# BreaV7.net
KiCad netlist of a schematic drawn in EAGLE
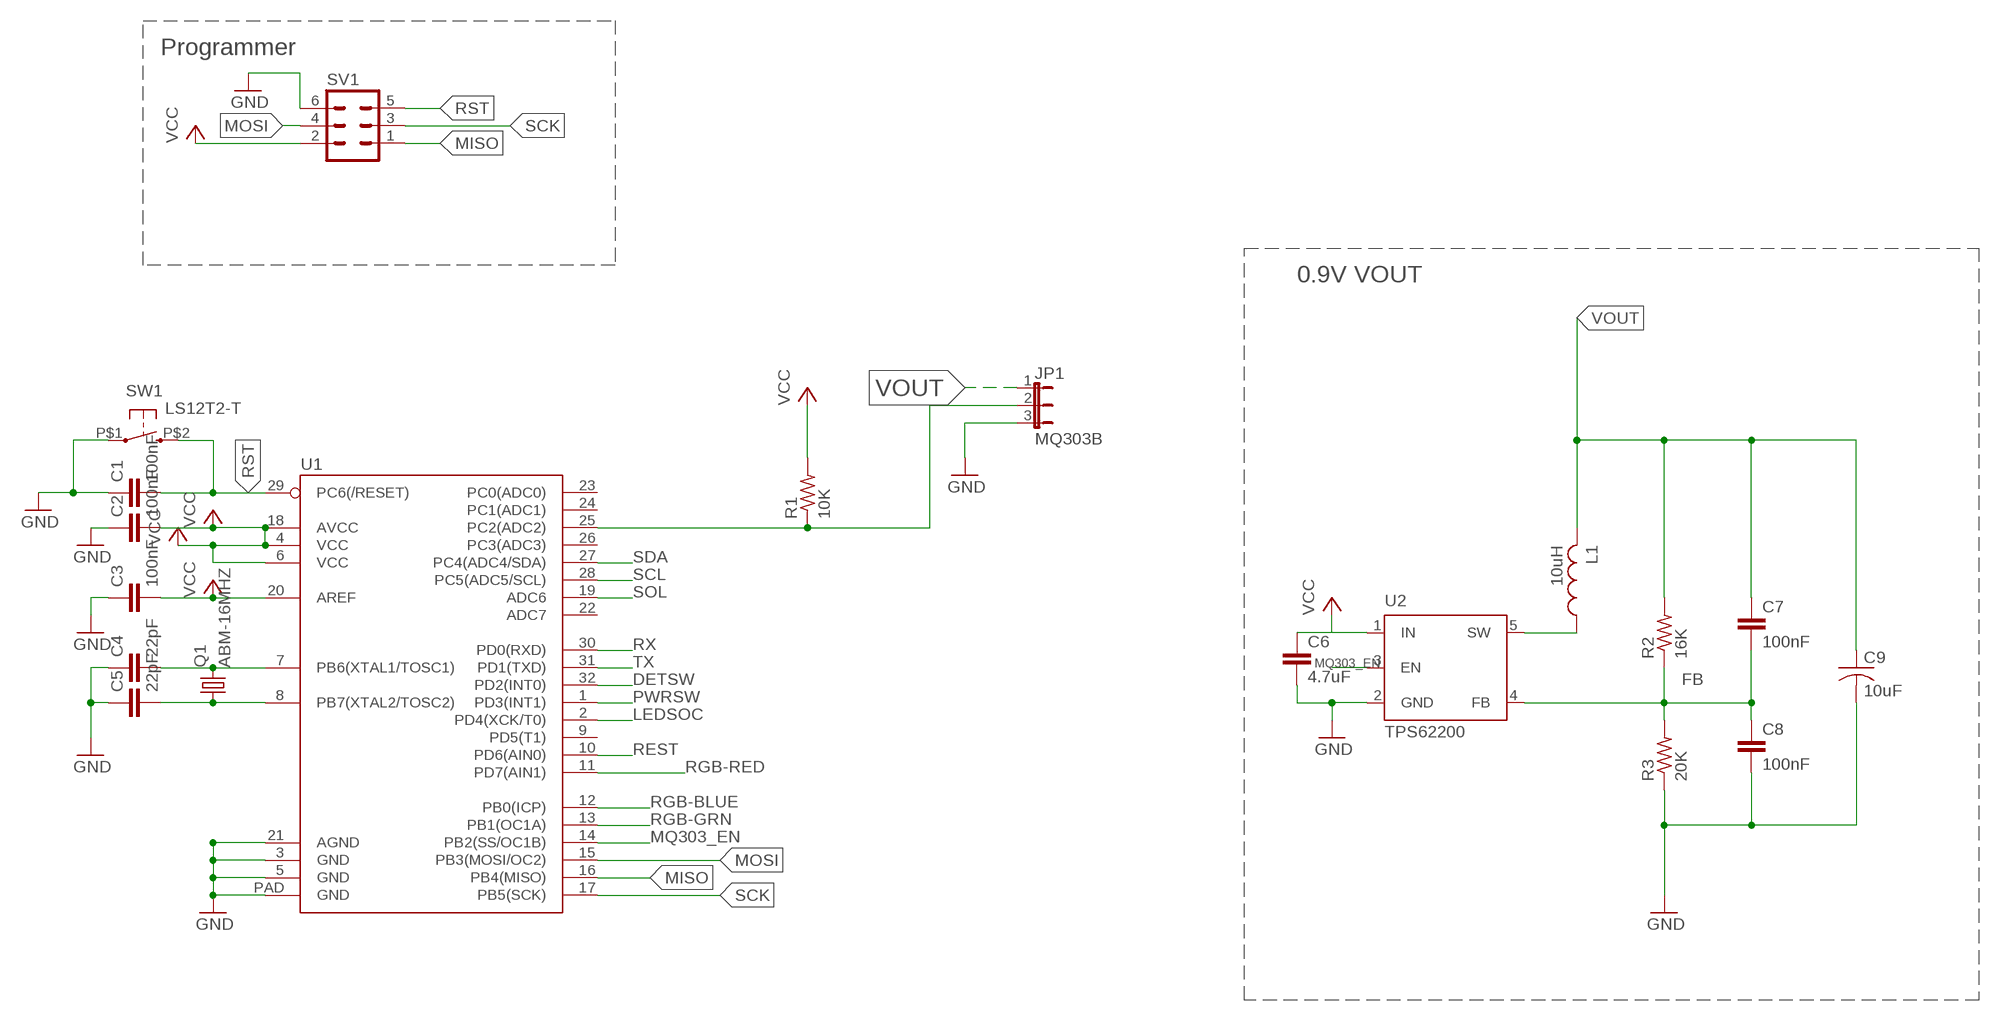
[diagram p0: schematic, sheet 1]
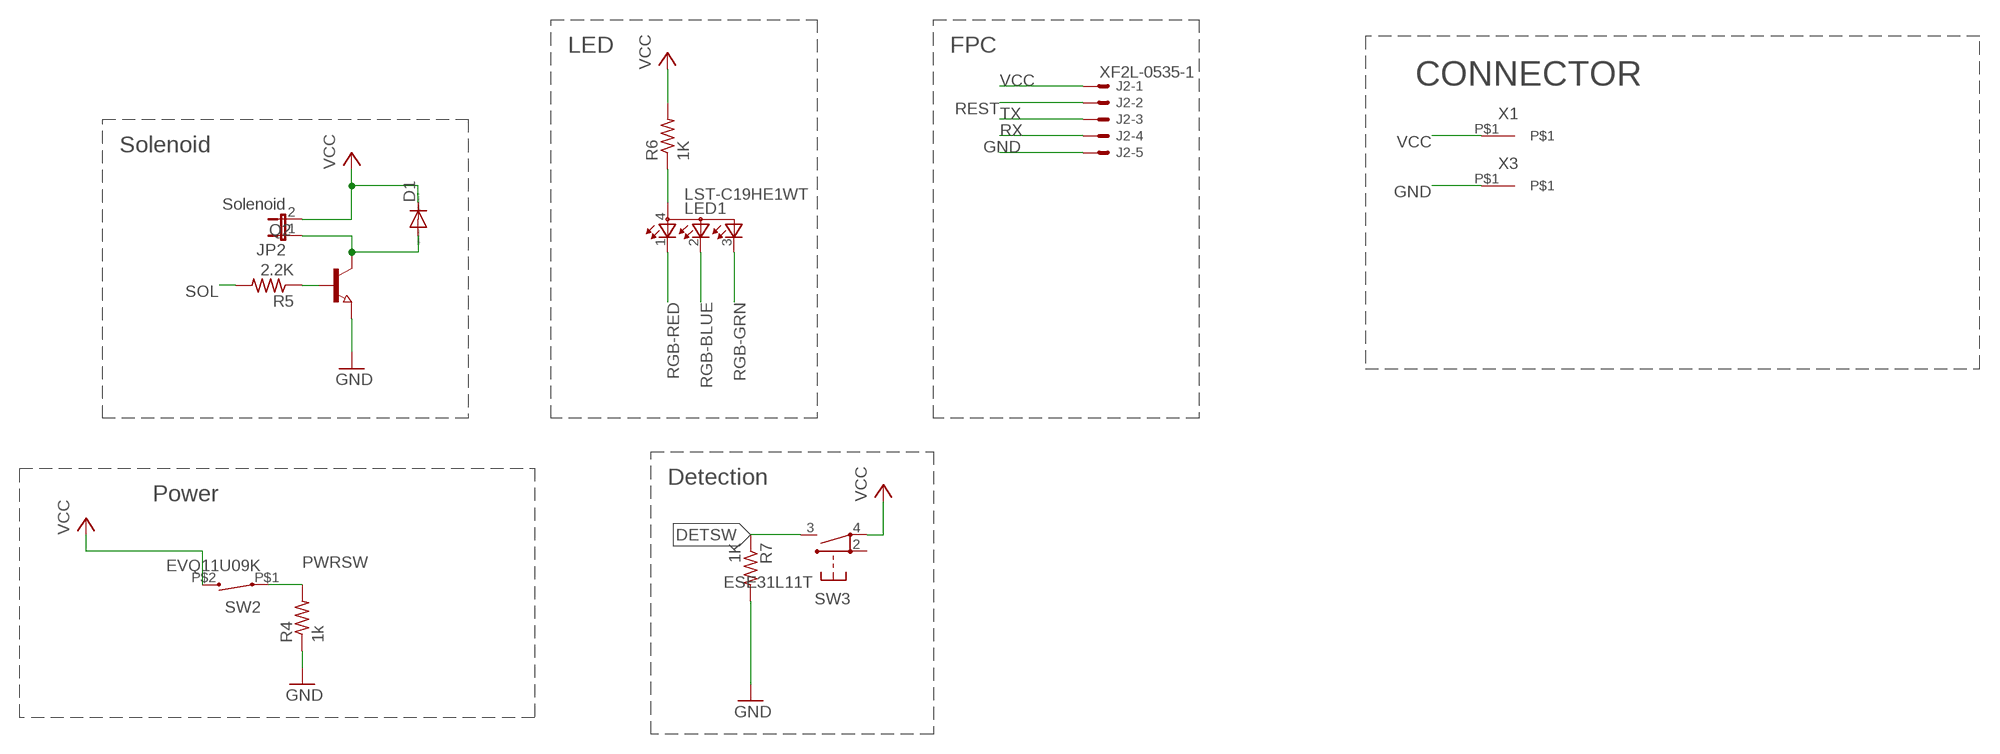
[diagram p1: schematic, sheet 2]
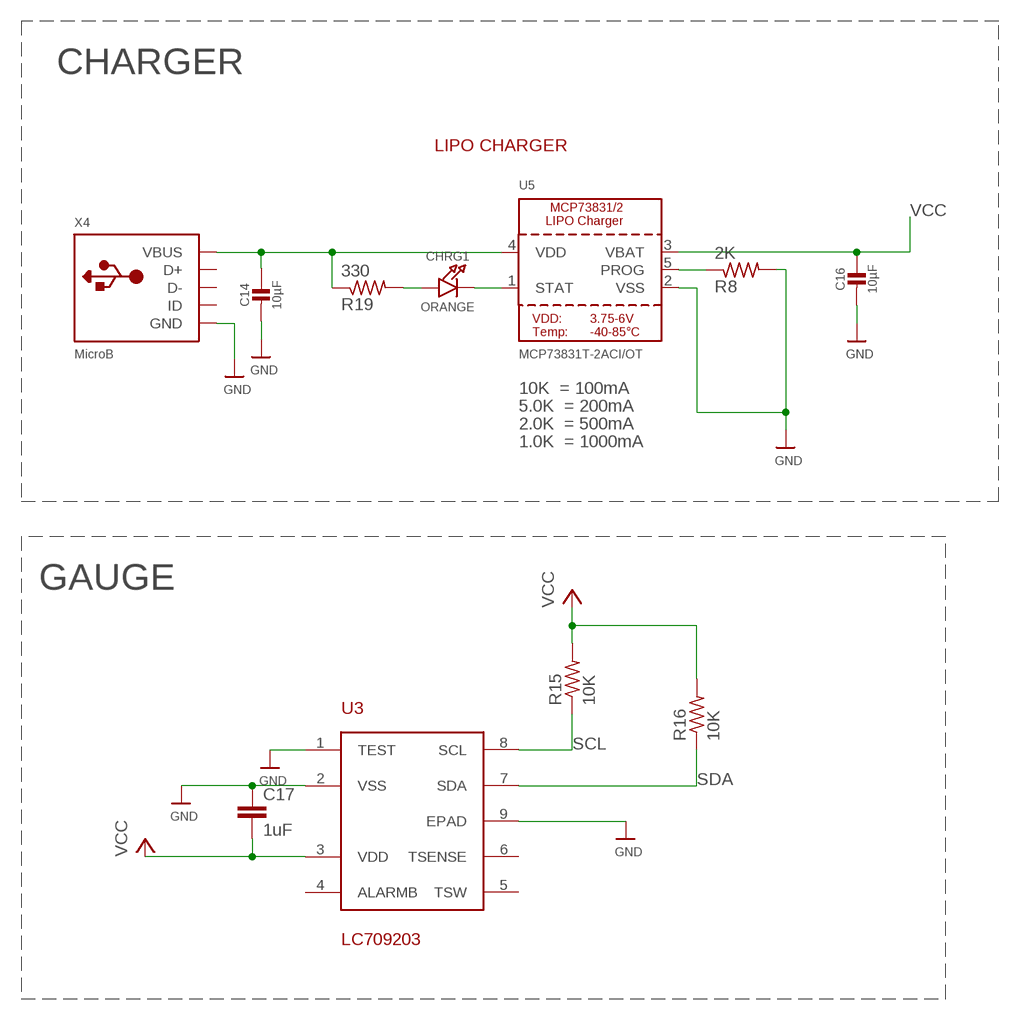
[diagram p2: schematic, sheet 3]

(export (version "E")
  (design (tool "Eeschema 10.0.6"))
  (components
    (comp (ref "C1")
      (value "100nF")
      (footprint "eagle-import:C0603")
      (libsource (lib "eagle-import") (part "C-EUC0603"))
    )
    (comp (ref "C2")
      (value "100nF")
      (footprint "eagle-import:C0603")
      (libsource (lib "eagle-import") (part "C-EUC0603"))
    )
    (comp (ref "C3")
      (value "100nF")
      (footprint "eagle-import:C0603")
      (libsource (lib "eagle-import") (part "C-EUC0603"))
    )
    (comp (ref "C4")
      (value "22pF")
      (footprint "eagle-import:C0603")
      (libsource (lib "eagle-import") (part "C-EUC0603"))
    )
    (comp (ref "C5")
      (value "22pF")
      (footprint "eagle-import:C0603")
      (libsource (lib "eagle-import") (part "C-EUC0603"))
    )
    (comp (ref "C6")
      (value "4.7uF")
      (footprint "eagle-import:C0402")
      (libsource (lib "eagle-import") (part "C-EUC0402"))
    )
    (comp (ref "C7")
      (value "100nF")
      (footprint "eagle-import:C0402")
      (libsource (lib "eagle-import") (part "C-EUC0402"))
    )
    (comp (ref "C8")
      (value "100nF")
      (footprint "eagle-import:C0402")
      (libsource (lib "eagle-import") (part "C-EUC0402"))
    )
    (comp (ref "C9")
      (value "10uF")
      (footprint "eagle-import:C0805K")
      (libsource (lib "eagle-import") (part "C-USC0805K"))
    )
    (comp (ref "JP1")
      (value "MQ303B")
      (footprint "eagle-import:JP2")
      (libsource (lib "eagle-import") (part "JP2E"))
    )
    (comp (ref "L1")
      (value "10uH")
      (footprint "eagle-import:L2825P")
      (libsource (lib "eagle-import") (part "L-USL2825P"))
    )
    (comp (ref "Q1")
      (value "ABM-16MHZ")
      (footprint "eagle-import:ABM-16MHZ")
      (libsource (lib "eagle-import") (part "ABM-16MHZ"))
    )
    (comp (ref "R1")
      (value "10K")
      (footprint "eagle-import:R0402")
      (libsource (lib "eagle-import") (part "R-US_R0402"))
    )
    (comp (ref "R2")
      (value "16K")
      (footprint "eagle-import:R0402")
      (libsource (lib "eagle-import") (part "R-US_R0402"))
    )
    (comp (ref "R3")
      (value "20K")
      (footprint "eagle-import:R0402")
      (libsource (lib "eagle-import") (part "R-US_R0402"))
    )
    (comp (ref "SV1")
      (value "MA03-2")
      (footprint "eagle-import:MA03-2")
      (libsource (lib "eagle-import") (part "MA03-2"))
    )
    (comp (ref "SW1")
      (value "LS12T2-T")
      (footprint "eagle-import:LS12T2-T")
      (libsource (lib "eagle-import") (part "LS12T2-T"))
    )
    (comp (ref "U1")
      (value "ATMEGA328P_MLFMLF32")
      (footprint "eagle-import:MLF32-PAD")
      (libsource (lib "eagle-import") (part "ATMEGA328P_MLFMLF32"))
    )
    (comp (ref "U2")
      (value "TPS62200")
      (footprint "eagle-import:TPS62200")
      (libsource (lib "eagle-import") (part "TPS62200"))
    )
    (comp (ref "C14")
      (value "10µF")
      (footprint "eagle-import:0805-NO")
      (libsource (lib "eagle-import") (part "CAP_CERAMIC0805-NOOUTLINE"))
    )
    (comp (ref "C16")
      (value "10µF")
      (footprint "eagle-import:0805-NO")
      (libsource (lib "eagle-import") (part "CAP_CERAMIC0805-NOOUTLINE"))
    )
    (comp (ref "C17")
      (value "1uF")
      (footprint "eagle-import:C0603")
      (libsource (lib "eagle-import") (part "C-EUC0603"))
    )
    (comp (ref "CHRG1")
      (value "ORANGE")
      (footprint "eagle-import:CHIPLED_0805_NOOUTLINE")
      (libsource (lib "eagle-import") (part "LED0805_NOOUTLINE"))
    )
    (comp (ref "R8")
      (value "2K")
      (footprint "eagle-import:R0402")
      (libsource (lib "eagle-import") (part "R-US_R0402"))
    )
    (comp (ref "R15")
      (value "10K")
      (footprint "eagle-import:R0402")
      (libsource (lib "eagle-import") (part "R-US_R0402"))
    )
    (comp (ref "R16")
      (value "10K")
      (footprint "eagle-import:R0402")
      (libsource (lib "eagle-import") (part "R-US_R0402"))
    )
    (comp (ref "R19")
      (value "330")
      (footprint "eagle-import:R0402")
      (libsource (lib "eagle-import") (part "R-US_R0402"))
    )
    (comp (ref "U3")
      (value "LC709203")
      (footprint "eagle-import:WDFN8")
      (libsource (lib "eagle-import") (part "LC709203"))
    )
    (comp (ref "U5")
      (value "MCP73831T-2ACI/OT")
      (footprint "eagle-import:SOT23-5")
      (libsource (lib "eagle-import") (part "MCP73831/2"))
    )
    (comp (ref "X4")
      (value "MicroB")
      (footprint "eagle-import:4UCONN_20329")
      (libsource (lib "eagle-import") (part "USBMICRO_20329"))
    )
    (comp (ref "D1")
      (value "DIODE-SOD123")
      (footprint "eagle-import:SOD123")
      (libsource (lib "eagle-import") (part "DIODE-SOD123"))
    )
    (comp (ref "J2")
      (value "XF2L-0535-1")
      (footprint "eagle-import:XF2L-0535-1")
      (libsource (lib "eagle-import") (part "XF2-05?35-1L"))
    )
    (comp (ref "JP2")
      (value "Solenoid")
      (footprint "eagle-import:JP1")
      (libsource (lib "eagle-import") (part "JP1E"))
    )
    (comp (ref "LED1")
      (value "LST-C19HE1WT")
      (footprint "eagle-import:LST-C19HE1WT")
      (libsource (lib "eagle-import") (part "LST-C19HE1WT"))
    )
    (comp (ref "Q2")
      (value "NPN-TRANSISTOR_SOT23")
      (footprint "eagle-import:SOT23")
      (libsource (lib "eagle-import") (part "NPN-TRANSISTOR_SOT23"))
    )
    (comp (ref "R4")
      (value "1k")
      (footprint "eagle-import:R0402")
      (libsource (lib "eagle-import") (part "R-US_R0402"))
    )
    (comp (ref "R5")
      (value "2.2K")
      (footprint "eagle-import:R0402")
      (libsource (lib "eagle-import") (part "R-US_R0402"))
    )
    (comp (ref "R6")
      (value "1K")
      (footprint "eagle-import:R0402")
      (libsource (lib "eagle-import") (part "R-US_R0402"))
    )
    (comp (ref "R7")
      (value "1K")
      (footprint "eagle-import:R0402")
      (libsource (lib "eagle-import") (part "R-US_R0402"))
    )
    (comp (ref "SW2")
      (value "EVQ11U09K")
      (footprint "eagle-import:EVQ11U-09K")
      (libsource (lib "eagle-import") (part "EVQ11U09K"))
    )
    (comp (ref "SW3")
      (value "ESE31L11T")
      (footprint "eagle-import:SWITCH")
      (libsource (lib "eagle-import") (part "ESE31L11T"))
    )
    (comp (ref "X1")
      (value "CON-1PIN")
      (footprint "eagle-import:CON-1PIN")
      (libsource (lib "eagle-import") (part "CON-1PIN"))
    )
    (comp (ref "X3")
      (value "CON-1PIN")
      (footprint "eagle-import:CON-1PIN")
      (libsource (lib "eagle-import") (part "CON-1PIN"))
    )
  )
  (nets
    (net (code "1") (name "DETSW") (class "Default")
      (node (ref "R7") (pin "1") (pinfunction "1_1") (pintype "passive"))
      (node (ref "SW3") (pin "3") (pinfunction "1_3") (pintype "passive"))
      (node (ref "U1") (pin "32") (pinfunction "PD2(INT0)_32") (pintype "bidirectional"))
    )
    (net (code "2") (name "FB") (class "Default")
      (node (ref "C7") (pin "2") (pinfunction "2_2") (pintype "passive"))
      (node (ref "C8") (pin "1") (pinfunction "1_1") (pintype "passive"))
      (node (ref "R2") (pin "1") (pinfunction "1_1") (pintype "passive"))
      (node (ref "R3") (pin "2") (pinfunction "2_2") (pintype "passive"))
      (node (ref "U2") (pin "4") (pinfunction "FB_4") (pintype "passive"))
    )
    (net (code "3") (name "GND") (class "Default")
      (node (ref "C1") (pin "1") (pinfunction "1_1") (pintype "passive"))
      (node (ref "C14") (pin "2") (pinfunction "2_2") (pintype "passive"))
      (node (ref "C16") (pin "2") (pinfunction "2_2") (pintype "passive"))
      (node (ref "C17") (pin "1") (pinfunction "1_1") (pintype "passive"))
      (node (ref "C2") (pin "1") (pinfunction "1_1") (pintype "passive"))
      (node (ref "C3") (pin "1") (pinfunction "1_1") (pintype "passive"))
      (node (ref "C4") (pin "1") (pinfunction "1_1") (pintype "passive"))
      (node (ref "C5") (pin "1") (pinfunction "1_1") (pintype "passive"))
      (node (ref "C6") (pin "2") (pinfunction "2_2") (pintype "passive"))
      (node (ref "C8") (pin "2") (pinfunction "2_2") (pintype "passive"))
      (node (ref "C9") (pin "2") (pinfunction "2_2") (pintype "passive"))
      (node (ref "J2") (pin "5") (pinfunction "MS_5") (pintype "passive"))
      (node (ref "JP1") (pin "3") (pinfunction "3_3") (pintype "passive"))
      (node (ref "Q2") (pin "2") (pinfunction "E_2") (pintype "passive"))
      (node (ref "R3") (pin "1") (pinfunction "1_1") (pintype "passive"))
      (node (ref "R4") (pin "1") (pinfunction "1_1") (pintype "passive"))
      (node (ref "R7") (pin "2") (pinfunction "2_2") (pintype "passive"))
      (node (ref "R8") (pin "2") (pinfunction "2_2") (pintype "passive"))
      (node (ref "SV1") (pin "6") (pinfunction "MISO_6") (pintype "passive"))
      (node (ref "SW1") (pin "P$1") (pinfunction "S1_P$1") (pintype "passive"))
      (node (ref "U1") (pin "21") (pinfunction "AGND_21") (pintype "bidirectional"))
      (node (ref "U1") (pin "3") (pinfunction "GND_3") (pintype "bidirectional"))
      (node (ref "U1") (pin "5") (pinfunction "GND_5") (pintype "bidirectional"))
      (node (ref "U1") (pin "PAD") (pinfunction "GND_PAD") (pintype "bidirectional"))
      (node (ref "U2") (pin "2") (pinfunction "GND_2") (pintype "power_in"))
      (node (ref "U3") (pin "1") (pinfunction "TEST_1") (pintype "bidirectional"))
      (node (ref "U3") (pin "2") (pinfunction "VSS_2") (pintype "bidirectional"))
      (node (ref "U3") (pin "9") (pinfunction "EPAD_9") (pintype "bidirectional"))
      (node (ref "U5") (pin "2") (pinfunction "VSS_2") (pintype "power_in"))
      (node (ref "X3") (pin "P$1") (pinfunction "P$1_P$1") (pintype "bidirectional"))
      (node (ref "X4") (pin "BASE@1") (pinfunction "GND_BASE@1") (pintype "power_in"))
      (node (ref "X4") (pin "BASE@2") (pinfunction "GND_BASE@2") (pintype "power_in"))
      (node (ref "X4") (pin "GND") (pinfunction "GND_GND") (pintype "power_in"))
      (node (ref "X4") (pin "SPRT@1") (pinfunction "GND_SPRT@1") (pintype "power_in"))
      (node (ref "X4") (pin "SPRT@2") (pinfunction "GND_SPRT@2") (pintype "power_in"))
      (node (ref "X4") (pin "SPRT@3") (pinfunction "GND_SPRT@3") (pintype "power_in"))
      (node (ref "X4") (pin "SPRT@4") (pinfunction "GND_SPRT@4") (pintype "power_in"))
    )
    (net (code "4") (name "LEDSOC") (class "Default")
      (node (ref "U1") (pin "2") (pinfunction "PD4(XCK/T0)_2") (pintype "bidirectional"))
    )
    (net (code "5") (name "MISO") (class "Default")
      (node (ref "SV1") (pin "1") (pinfunction "1_1") (pintype "passive"))
      (node (ref "U1") (pin "16") (pinfunction "PB4(MISO)_16") (pintype "bidirectional"))
    )
    (net (code "6") (name "MOSI") (class "Default")
      (node (ref "SV1") (pin "4") (pinfunction "4_4") (pintype "passive"))
      (node (ref "U1") (pin "15") (pinfunction "PB3(MOSI/OC2)_15") (pintype "bidirectional"))
    )
    (net (code "7") (name "MQ303_EN") (class "Default")
      (node (ref "U1") (pin "14") (pinfunction "PB2(SS/OC1B)_14") (pintype "bidirectional"))
      (node (ref "U2") (pin "3") (pinfunction "EN_3") (pintype "input"))
    )
    (net (code "8") (name "Net-(CHRG1-PadA)") (class "Default")
      (node (ref "CHRG1") (pin "A") (pinfunction "A_A") (pintype "passive"))
      (node (ref "R19") (pin "2") (pinfunction "2_2") (pintype "passive"))
    )
    (net (code "9") (name "Net-(LED1-A)") (class "Default")
      (node (ref "LED1") (pin "4") (pinfunction "A_4") (pintype "passive"))
      (node (ref "R6") (pin "1") (pinfunction "1_1") (pintype "passive"))
    )
    (net (code "10") (name "Net-(Q1-1)") (class "Default")
      (node (ref "C5") (pin "2") (pinfunction "2_2") (pintype "passive"))
      (node (ref "Q1") (pin "P$1") (pinfunction "1_P$1") (pintype "passive"))
      (node (ref "U1") (pin "8") (pinfunction "PB7(XTAL2/TOSC2)_8") (pintype "bidirectional"))
    )
    (net (code "11") (name "Net-(Q1-2)") (class "Default")
      (node (ref "C4") (pin "2") (pinfunction "2_2") (pintype "passive"))
      (node (ref "Q1") (pin "P$2") (pinfunction "2_P$2") (pintype "passive"))
      (node (ref "U1") (pin "7") (pinfunction "PB6(XTAL1/TOSC1)_7") (pintype "bidirectional"))
    )
    (net (code "12") (name "Net-(Q2-B)") (class "Default")
      (node (ref "Q2") (pin "1") (pinfunction "B_1") (pintype "passive"))
      (node (ref "R5") (pin "1") (pinfunction "1_1") (pintype "passive"))
    )
    (net (code "13") (name "Net-(Q2-C)") (class "Default")
      (node (ref "D1") (pin "A") (pinfunction "A_A") (pintype "passive"))
      (node (ref "JP2") (pin "1") (pinfunction "1_1") (pintype "passive"))
      (node (ref "Q2") (pin "3") (pinfunction "C_3") (pintype "passive"))
    )
    (net (code "14") (name "Net-(U1-PC2(ADC2))") (class "Default")
      (node (ref "JP1") (pin "2") (pinfunction "2_2") (pintype "passive"))
      (node (ref "R1") (pin "1") (pinfunction "1_1") (pintype "passive"))
      (node (ref "U1") (pin "25") (pinfunction "PC2(ADC2)_25") (pintype "bidirectional"))
    )
    (net (code "15") (name "Net-(U2-IN)") (class "Default")
      (node (ref "C6") (pin "1") (pinfunction "1_1") (pintype "passive"))
      (node (ref "U2") (pin "1") (pinfunction "IN_1") (pintype "input"))
    )
    (net (code "16") (name "Net-(U2-SW)") (class "Default")
      (node (ref "L1") (pin "1") (pinfunction "1_1") (pintype "passive"))
      (node (ref "U2") (pin "5") (pinfunction "SW_5") (pintype "passive"))
    )
    (net (code "17") (name "Net-(U5-PROG)") (class "Default")
      (node (ref "R8") (pin "1") (pinfunction "1_1") (pintype "passive"))
      (node (ref "U5") (pin "5") (pinfunction "PROG_5") (pintype "input"))
    )
    (net (code "18") (name "Net-(U5-STAT)") (class "Default")
      (node (ref "CHRG1") (pin "C") (pinfunction "C_C") (pintype "passive"))
      (node (ref "U5") (pin "1") (pinfunction "STAT_1") (pintype "output"))
    )
    (net (code "19") (name "Net-(U5-VDD)") (class "Default")
      (node (ref "C14") (pin "1") (pinfunction "1_1") (pintype "passive"))
      (node (ref "R19") (pin "1") (pinfunction "1_1") (pintype "passive"))
      (node (ref "U5") (pin "4") (pinfunction "VDD_4") (pintype "power_in"))
      (node (ref "X4") (pin "VBUS") (pinfunction "VBUS_VBUS") (pintype "power_in"))
    )
    (net (code "20") (name "PWRSW") (class "Default")
      (node (ref "R4") (pin "2") (pinfunction "2_2") (pintype "passive"))
      (node (ref "SW2") (pin "P$1") (pinfunction "1_P$1") (pintype "passive"))
      (node (ref "U1") (pin "1") (pinfunction "PD3(INT1)_1") (pintype "bidirectional"))
    )
    (net (code "21") (name "REST") (class "Default")
      (node (ref "J2") (pin "2") (pinfunction "MS_2") (pintype "passive"))
      (node (ref "U1") (pin "10") (pinfunction "PD6(AIN0)_10") (pintype "bidirectional"))
    )
    (net (code "22") (name "RGB-BLUE") (class "Default")
      (node (ref "LED1") (pin "2") (pinfunction "CGREEN_2") (pintype "passive"))
      (node (ref "U1") (pin "12") (pinfunction "PB0(ICP)_12") (pintype "bidirectional"))
    )
    (net (code "23") (name "RGB-GRN") (class "Default")
      (node (ref "LED1") (pin "3") (pinfunction "CBLUE_3") (pintype "passive"))
      (node (ref "U1") (pin "13") (pinfunction "PB1(OC1A)_13") (pintype "bidirectional"))
    )
    (net (code "24") (name "RGB-RED") (class "Default")
      (node (ref "LED1") (pin "1") (pinfunction "CRED_1") (pintype "passive"))
      (node (ref "U1") (pin "11") (pinfunction "PD7(AIN1)_11") (pintype "bidirectional"))
    )
    (net (code "25") (name "RST") (class "Default")
      (node (ref "C1") (pin "2") (pinfunction "2_2") (pintype "passive"))
      (node (ref "SV1") (pin "5") (pinfunction "VTG_5") (pintype "passive"))
      (node (ref "SW1") (pin "P$2") (pinfunction "S2_P$2") (pintype "passive"))
      (node (ref "U1") (pin "29") (pinfunction "PC6(/RESET)_29") (pintype "bidirectional"))
    )
    (net (code "26") (name "RX") (class "Default")
      (node (ref "J2") (pin "4") (pinfunction "MS_4") (pintype "passive"))
      (node (ref "U1") (pin "30") (pinfunction "PD0(RXD)_30") (pintype "bidirectional"))
    )
    (net (code "27") (name "SCK") (class "Default")
      (node (ref "SV1") (pin "3") (pinfunction "3_3") (pintype "passive"))
      (node (ref "U1") (pin "17") (pinfunction "PB5(SCK)_17") (pintype "bidirectional"))
    )
    (net (code "28") (name "SCL") (class "Default")
      (node (ref "R15") (pin "1") (pinfunction "1_1") (pintype "passive"))
      (node (ref "U1") (pin "28") (pinfunction "PC5(ADC5/SCL)_28") (pintype "bidirectional"))
      (node (ref "U3") (pin "8") (pinfunction "SCL_8") (pintype "bidirectional"))
    )
    (net (code "29") (name "SDA") (class "Default")
      (node (ref "R16") (pin "1") (pinfunction "1_1") (pintype "passive"))
      (node (ref "U1") (pin "27") (pinfunction "PC4(ADC4/SDA)_27") (pintype "bidirectional"))
      (node (ref "U3") (pin "7") (pinfunction "SDA_7") (pintype "bidirectional"))
    )
    (net (code "30") (name "SOL") (class "Default")
      (node (ref "R5") (pin "2") (pinfunction "2_2") (pintype "passive"))
      (node (ref "U1") (pin "19") (pinfunction "ADC6_19") (pintype "bidirectional"))
    )
    (net (code "31") (name "TX") (class "Default")
      (node (ref "J2") (pin "3") (pinfunction "MS_3") (pintype "passive"))
      (node (ref "U1") (pin "31") (pinfunction "PD1(TXD)_31") (pintype "bidirectional"))
    )
    (net (code "32") (name "VCC") (class "Default")
      (node (ref "C16") (pin "1") (pinfunction "1_1") (pintype "passive"))
      (node (ref "C17") (pin "2") (pinfunction "2_2") (pintype "passive"))
      (node (ref "C2") (pin "2") (pinfunction "2_2") (pintype "passive"))
      (node (ref "C3") (pin "2") (pinfunction "2_2") (pintype "passive"))
      (node (ref "D1") (pin "C") (pinfunction "C_C") (pintype "passive"))
      (node (ref "J2") (pin "1") (pinfunction "MSV_1") (pintype "passive"))
      (node (ref "JP2") (pin "2") (pinfunction "2_2") (pintype "passive"))
      (node (ref "R1") (pin "2") (pinfunction "2_2") (pintype "passive"))
      (node (ref "R15") (pin "2") (pinfunction "2_2") (pintype "passive"))
      (node (ref "R16") (pin "2") (pinfunction "2_2") (pintype "passive"))
      (node (ref "R6") (pin "2") (pinfunction "2_2") (pintype "passive"))
      (node (ref "SV1") (pin "2") (pinfunction "2_2") (pintype "passive"))
      (node (ref "SW2") (pin "P$2") (pinfunction "2_P$2") (pintype "passive"))
      (node (ref "SW3") (pin "4") (pinfunction "C3_4") (pintype "passive"))
      (node (ref "U1") (pin "18") (pinfunction "AVCC_18") (pintype "bidirectional"))
      (node (ref "U1") (pin "20") (pinfunction "AREF_20") (pintype "bidirectional"))
      (node (ref "U1") (pin "4") (pinfunction "VCC_4") (pintype "bidirectional"))
      (node (ref "U1") (pin "6") (pinfunction "VCC_6") (pintype "bidirectional"))
      (node (ref "U3") (pin "3") (pinfunction "VDD_3") (pintype "bidirectional"))
      (node (ref "U5") (pin "3") (pinfunction "VBAT_3") (pintype "power_in"))
      (node (ref "X1") (pin "P$1") (pinfunction "P$1_P$1") (pintype "bidirectional"))
    )
    (net (code "33") (name "VOUT") (class "Default")
      (node (ref "C7") (pin "1") (pinfunction "1_1") (pintype "passive"))
      (node (ref "C9") (pin "1") (pinfunction "1_1") (pintype "passive"))
      (node (ref "JP1") (pin "1") (pinfunction "1_1") (pintype "passive"))
      (node (ref "L1") (pin "2") (pinfunction "2_2") (pintype "passive"))
      (node (ref "R2") (pin "2") (pinfunction "2_2") (pintype "passive"))
    )
    (net (code "34") (name "unconnected-(SW3-C2-Pad2)") (class "Default")
      (node (ref "SW3") (pin "2") (pinfunction "C2_2") (pintype "passive"))
    )
    (net (code "35") (name "unconnected-(U1-ADC7-Pad22)") (class "Default")
      (node (ref "U1") (pin "22") (pinfunction "ADC7_22") (pintype "bidirectional"))
    )
    (net (code "36") (name "unconnected-(U1-PC0(ADC0)-Pad23)") (class "Default")
      (node (ref "U1") (pin "23") (pinfunction "PC0(ADC0)_23") (pintype "bidirectional"))
    )
    (net (code "37") (name "unconnected-(U1-PC1(ADC1)-Pad24)") (class "Default")
      (node (ref "U1") (pin "24") (pinfunction "PC1(ADC1)_24") (pintype "bidirectional"))
    )
    (net (code "38") (name "unconnected-(U1-PC3(ADC3)-Pad26)") (class "Default")
      (node (ref "U1") (pin "26") (pinfunction "PC3(ADC3)_26") (pintype "bidirectional"))
    )
    (net (code "39") (name "unconnected-(U1-PD5(T1)-Pad9)") (class "Default")
      (node (ref "U1") (pin "9") (pinfunction "PD5(T1)_9") (pintype "bidirectional"))
    )
    (net (code "40") (name "unconnected-(U3-ALARMB-Pad4)") (class "Default")
      (node (ref "U3") (pin "4") (pinfunction "ALARMB_4") (pintype "bidirectional"))
    )
    (net (code "41") (name "unconnected-(U3-TSENSE-Pad6)") (class "Default")
      (node (ref "U3") (pin "6") (pinfunction "TSENSE_6") (pintype "bidirectional"))
    )
    (net (code "42") (name "unconnected-(U3-TSW-Pad5)") (class "Default")
      (node (ref "U3") (pin "5") (pinfunction "TSW_5") (pintype "bidirectional"))
    )
    (net (code "43") (name "unconnected-(X4-PadD+)") (class "Default")
      (node (ref "X4") (pin "D+") (pinfunction "D+_D+") (pintype "bidirectional"))
    )
    (net (code "44") (name "unconnected-(X4-PadD-)") (class "Default")
      (node (ref "X4") (pin "D-") (pinfunction "D-_D-") (pintype "bidirectional"))
    )
    (net (code "45") (name "unconnected-(X4-PadID)") (class "Default")
      (node (ref "X4") (pin "ID") (pinfunction "ID_ID") (pintype "bidirectional"))
    )
  )
)
